# doorbell.net
KiCad netlist of a schematic drawn in EAGLE
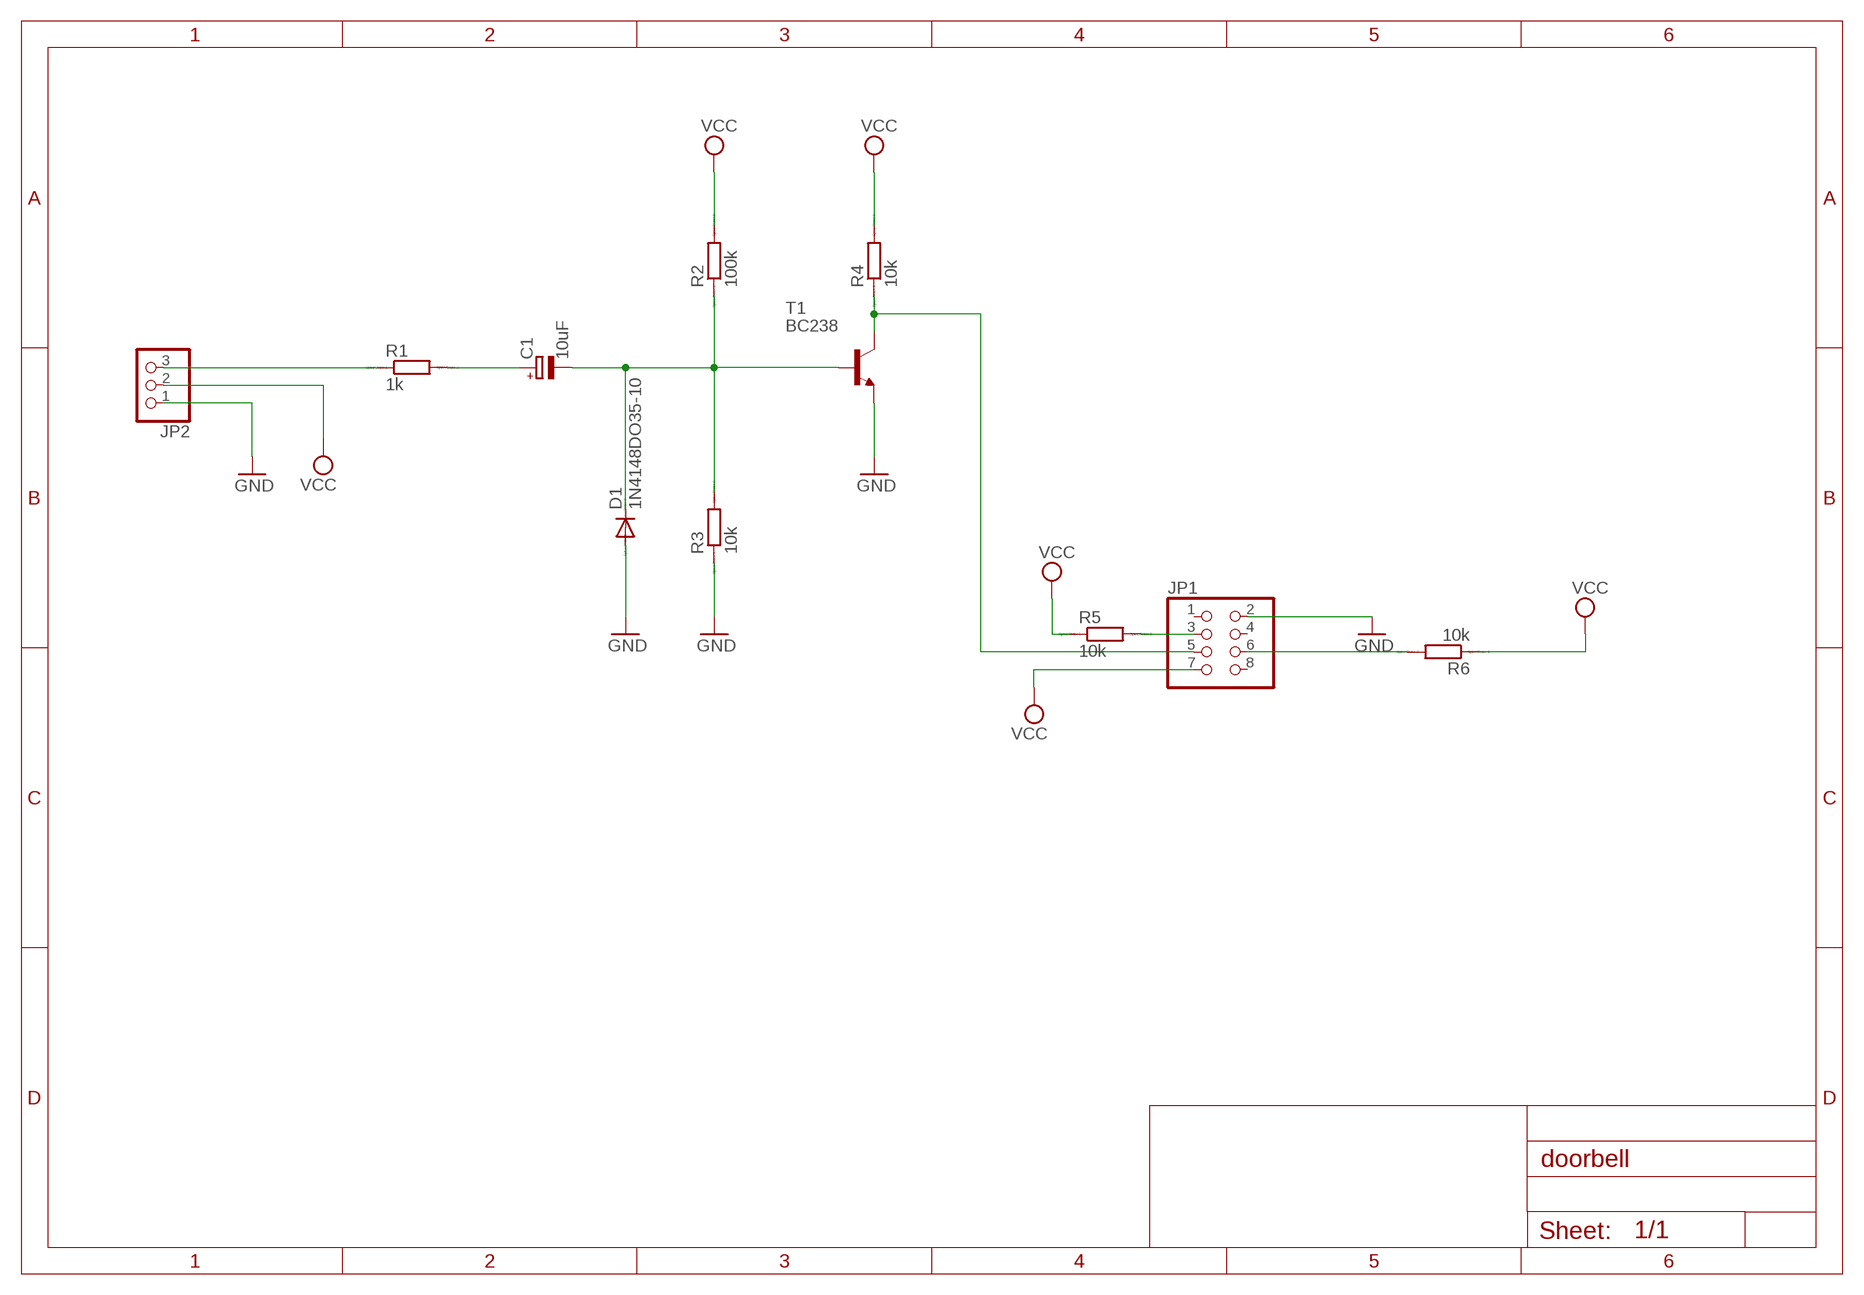
[diagram p0: schematic, sheet 1]

(export (version "E")
  (design (tool "Eeschema 10.0.6"))
  (components
    (comp (ref "C1")
      (value "10uF")
      (footprint "eagle-import:E2,5-6E")
      (libsource (lib "eagle-import") (part "CPOL-EUE2,5-6E"))
    )
    (comp (ref "D1")
      (value "1N4148DO35-10")
      (footprint "eagle-import:DO35-10")
      (libsource (lib "eagle-import") (part "1N4148DO35-10"))
    )
    (comp (ref "JP1")
      (value "PINHD-2X4")
      (footprint "eagle-import:2X04")
      (libsource (lib "eagle-import") (part "PINHD-2X4"))
    )
    (comp (ref "JP2")
      (value "PINHD-1X3")
      (footprint "eagle-import:1X03")
      (libsource (lib "eagle-import") (part "PINHD-1X3"))
    )
    (comp (ref "R1")
      (value "1k")
      (footprint "eagle-import:0207_10")
      (libsource (lib "eagle-import") (part "R0207/10"))
    )
    (comp (ref "R2")
      (value "100k")
      (footprint "eagle-import:0207_10")
      (libsource (lib "eagle-import") (part "R0207/10"))
    )
    (comp (ref "R3")
      (value "10k")
      (footprint "eagle-import:0207_10")
      (libsource (lib "eagle-import") (part "R0207/10"))
    )
    (comp (ref "R4")
      (value "10k")
      (footprint "eagle-import:0207_10")
      (libsource (lib "eagle-import") (part "R0207/10"))
    )
    (comp (ref "R5")
      (value "10k")
      (footprint "eagle-import:0207_10")
      (libsource (lib "eagle-import") (part "R0207/10"))
    )
    (comp (ref "R6")
      (value "10k")
      (footprint "eagle-import:0207_10")
      (libsource (lib "eagle-import") (part "R0207/10"))
    )
    (comp (ref "T1")
      (value "BC238")
      (footprint "eagle-import:TO92")
      (libsource (lib "eagle-import") (part "BC238"))
    )
  )
  (nets
    (net (code "1") (name "GND") (class "Default")
      (node (ref "D1") (pin "A") (pinfunction "A_A") (pintype "passive"))
      (node (ref "JP1") (pin "2") (pinfunction "2_2") (pintype "passive"))
      (node (ref "JP2") (pin "1") (pinfunction "1_1") (pintype "passive"))
      (node (ref "R3") (pin "1") (pinfunction "1_1") (pintype "passive"))
      (node (ref "T1") (pin "1") (pinfunction "E_1") (pintype "passive"))
    )
    (net (code "2") (name "Net-(C1-Pad+)") (class "Default")
      (node (ref "C1") (pin "+") (pinfunction "+_+") (pintype "passive"))
      (node (ref "R1") (pin "2") (pinfunction "2_2") (pintype "passive"))
    )
    (net (code "3") (name "Net-(JP1-Pad3)") (class "Default")
      (node (ref "JP1") (pin "3") (pinfunction "3_3") (pintype "passive"))
      (node (ref "R5") (pin "2") (pinfunction "2_2") (pintype "passive"))
    )
    (net (code "4") (name "Net-(JP1-Pad6)") (class "Default")
      (node (ref "JP1") (pin "6") (pinfunction "6_6") (pintype "passive"))
      (node (ref "R6") (pin "2") (pinfunction "2_2") (pintype "passive"))
    )
    (net (code "5") (name "Net-(JP2-Pad3)") (class "Default")
      (node (ref "JP2") (pin "3") (pinfunction "3_3") (pintype "passive"))
      (node (ref "R1") (pin "1") (pinfunction "1_1") (pintype "passive"))
    )
    (net (code "6") (name "Net-(T1-B)") (class "Default")
      (node (ref "C1") (pin "-") (pinfunction "-_-") (pintype "passive"))
      (node (ref "D1") (pin "C") (pinfunction "C_C") (pintype "passive"))
      (node (ref "R2") (pin "1") (pinfunction "1_1") (pintype "passive"))
      (node (ref "R3") (pin "2") (pinfunction "2_2") (pintype "passive"))
      (node (ref "T1") (pin "2") (pinfunction "B_2") (pintype "passive"))
    )
    (net (code "7") (name "Net-(T1-C)") (class "Default")
      (node (ref "JP1") (pin "5") (pinfunction "5_5") (pintype "passive"))
      (node (ref "R4") (pin "1") (pinfunction "1_1") (pintype "passive"))
      (node (ref "T1") (pin "3") (pinfunction "C_3") (pintype "passive"))
    )
    (net (code "8") (name "VCC") (class "Default")
      (node (ref "JP1") (pin "7") (pinfunction "7_7") (pintype "passive"))
      (node (ref "JP2") (pin "2") (pinfunction "2_2") (pintype "passive"))
      (node (ref "R2") (pin "2") (pinfunction "2_2") (pintype "passive"))
      (node (ref "R4") (pin "2") (pinfunction "2_2") (pintype "passive"))
      (node (ref "R5") (pin "1") (pinfunction "1_1") (pintype "passive"))
      (node (ref "R6") (pin "1") (pinfunction "1_1") (pintype "passive"))
    )
    (net (code "9") (name "unconnected-(JP1-Pad1)") (class "Default")
      (node (ref "JP1") (pin "1") (pinfunction "1_1") (pintype "passive"))
    )
    (net (code "10") (name "unconnected-(JP1-Pad4)") (class "Default")
      (node (ref "JP1") (pin "4") (pinfunction "4_4") (pintype "passive"))
    )
    (net (code "11") (name "unconnected-(JP1-Pad8)") (class "Default")
      (node (ref "JP1") (pin "8") (pinfunction "8_8") (pintype "passive"))
    )
  )
)
